# switch_eval_box_redo_v2-1.net
KiCad netlist of a schematic drawn in EAGLE
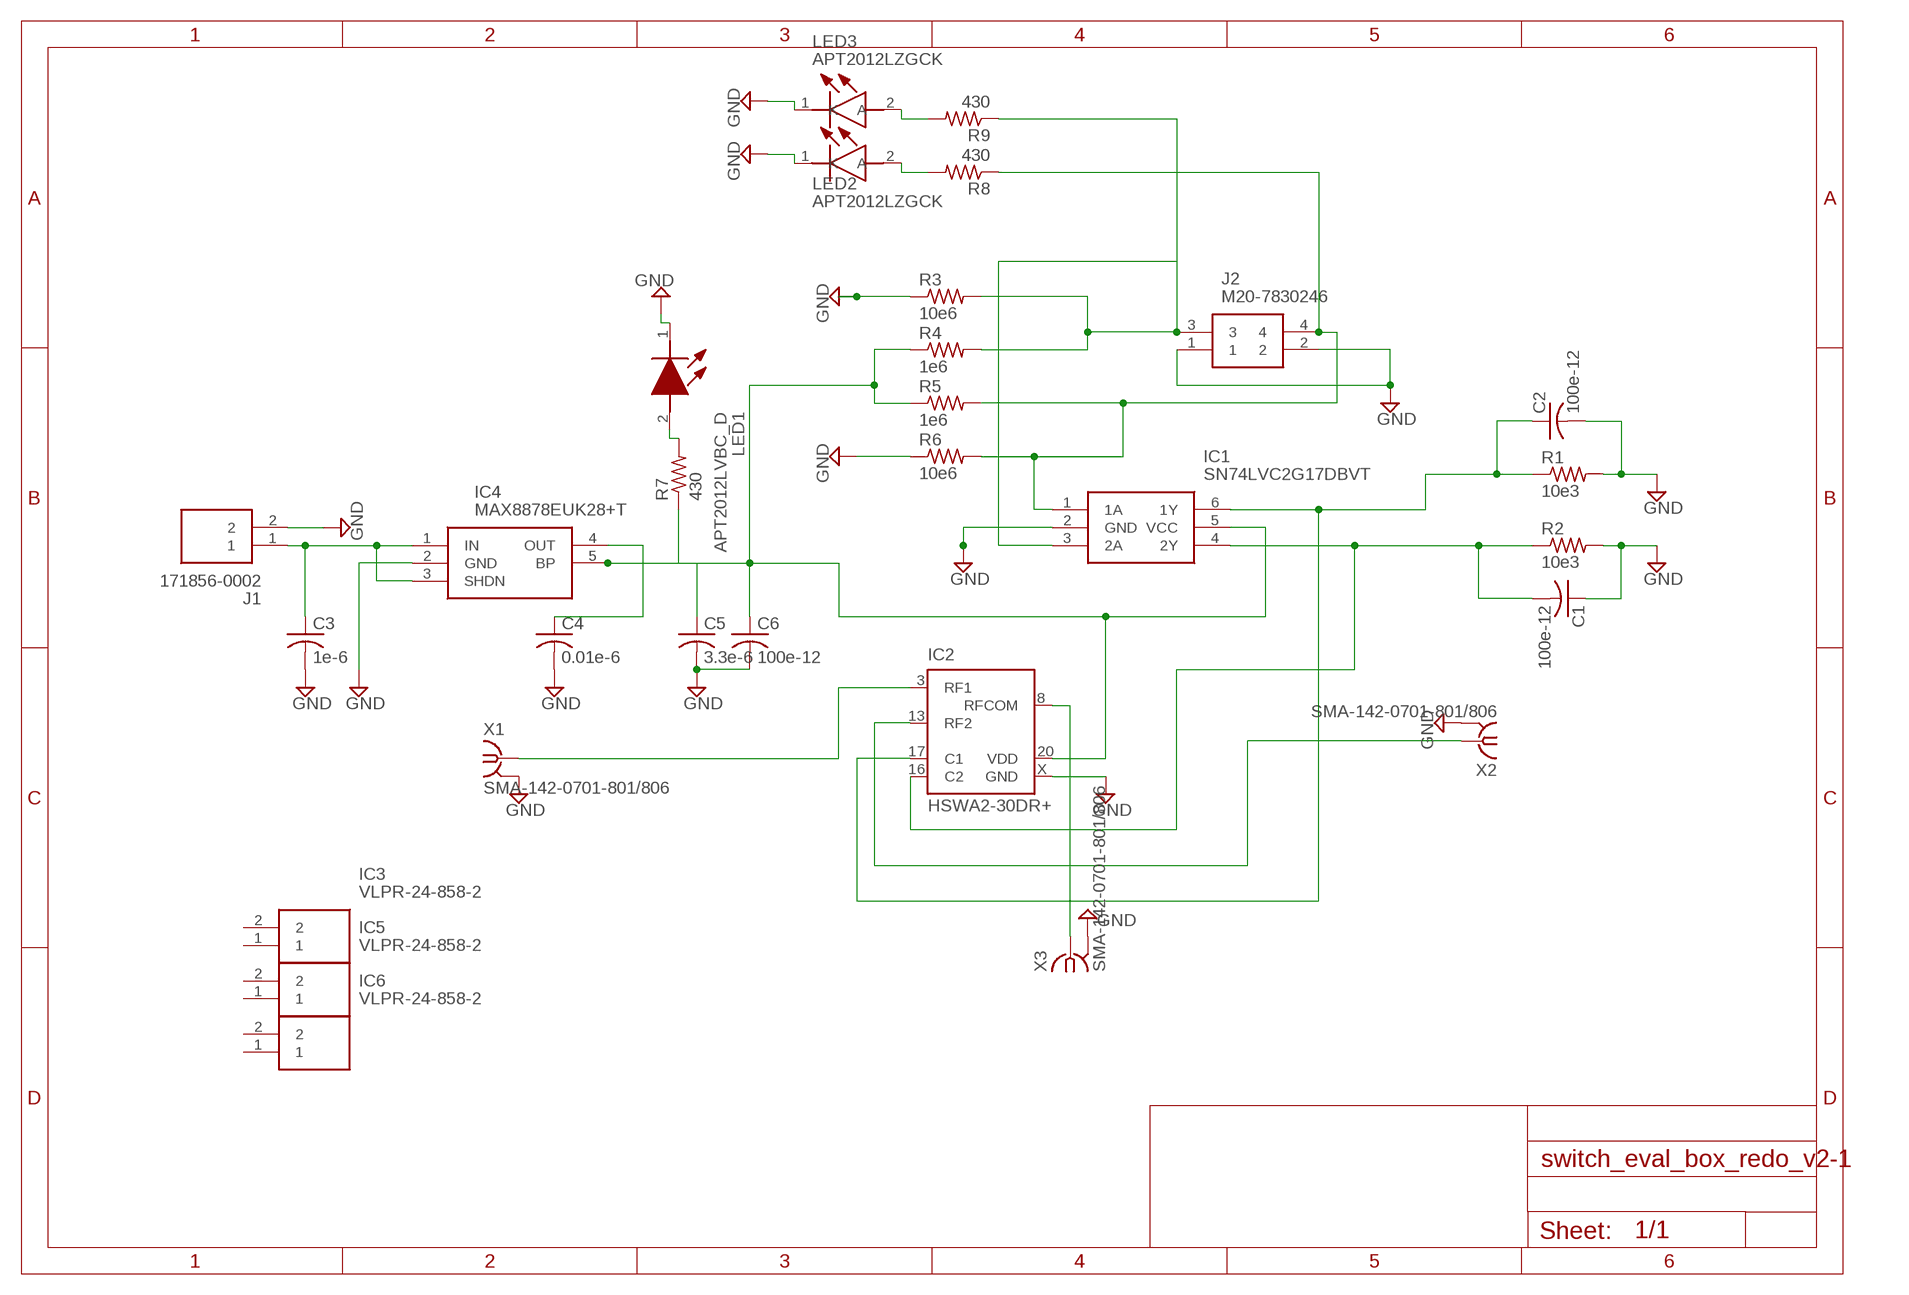
[diagram p0: schematic, sheet 1]

(export (version "E")
  (design (tool "Eeschema 10.0.6"))
  (components
    (comp (ref "C1")
      (value "100e-12")
      (footprint "eagle-import:C0603")
      (libsource (lib "eagle-import") (part "C-USC0603"))
    )
    (comp (ref "C2")
      (value "100e-12")
      (footprint "eagle-import:C0603")
      (libsource (lib "eagle-import") (part "C-USC0603"))
    )
    (comp (ref "C3")
      (value "1e-6")
      (footprint "eagle-import:C0603")
      (libsource (lib "eagle-import") (part "C-USC0603"))
    )
    (comp (ref "C4")
      (value "0.01e-6")
      (footprint "eagle-import:C0603")
      (libsource (lib "eagle-import") (part "C-USC0603"))
    )
    (comp (ref "C5")
      (value "3.3e-6")
      (footprint "eagle-import:C0603")
      (libsource (lib "eagle-import") (part "C-USC0603"))
    )
    (comp (ref "C6")
      (value "100e-12")
      (footprint "eagle-import:C0603")
      (libsource (lib "eagle-import") (part "C-USC0603"))
    )
    (comp (ref "IC1")
      (value "SN74LVC2G17DBVT")
      (footprint "eagle-import:SOT95P280X145-6N")
      (fields
        (field (name "MOUSER_PART_NUMBER") "595-SN74LVC2G17DBVT")
        (field (name "RS_PART_NUMBER") "6628944P")
      )
      (libsource (lib "eagle-import") (part "SN74LVC2G17DBVT"))
    )
    (comp (ref "IC2")
      (value "HSWA2-30DR+")
      (footprint "eagle-import:DG983-1")
      (libsource (lib "eagle-import") (part "HSWA2-30DR+"))
    )
    (comp (ref "IC3")
      (value "VLPR-24-858-2")
      (footprint "eagle-import:VLPR248582")
      (fields (field (name "RS_PART_NUMBER") "9063748"))
      (libsource (lib "eagle-import") (part "VLPR-24-858-2"))
    )
    (comp (ref "IC4")
      (value "MAX8878EUK28+T")
      (footprint "eagle-import:SOT95P280X145-5N")
      (libsource (lib "eagle-import") (part "MAX8878EUK28+T"))
    )
    (comp (ref "IC5")
      (value "VLPR-24-858-2")
      (footprint "eagle-import:VLPR248582")
      (fields (field (name "RS_PART_NUMBER") "9063748"))
      (libsource (lib "eagle-import") (part "VLPR-24-858-2"))
    )
    (comp (ref "IC6")
      (value "VLPR-24-858-2")
      (footprint "eagle-import:VLPR248582")
      (fields (field (name "RS_PART_NUMBER") "9063748"))
      (libsource (lib "eagle-import") (part "VLPR-24-858-2"))
    )
    (comp (ref "J1")
      (value "171856-0002")
      (footprint "eagle-import:SHDR2W90P0X254_1X2_493X635X106")
      (fields
        (field (name "MOUSER_PART_NUMBER") "538-171856-0002")
        (field (name "RS_PART_NUMBER") "7922884P")
      )
      (libsource (lib "eagle-import") (part "171856-0002"))
    )
    (comp (ref "J2")
      (value "M20-7830246")
      (footprint "eagle-import:M207830246")
      (fields
        (field (name "MOUSER_PART_NUMBER") "855-M20-7830246")
        (field (name "RS_PART_NUMBER") "6816839P")
      )
      (libsource (lib "eagle-import") (part "M20-7830246"))
    )
    (comp (ref "LED1")
      (value "APT2012LVBC_D")
      (footprint "eagle-import:LEDC2012X85N")
      (fields
        (field (name "ARROW_PART_NUMBER") "APT2012LVBC/D")
        (field (name "MOUSER_PART_NUMBER") "604-APT2012LVBCD")
      )
      (libsource (lib "eagle-import") (part "APT2012LVBC_D"))
    )
    (comp (ref "LED2")
      (value "APT2012LZGCK")
      (footprint "eagle-import:LEDC2012X85N")
      (fields (field (name "MOUSER_PART_NUMBER") "604-APT2012LZGCK"))
      (libsource (lib "eagle-import") (part "APT2012LZGCK"))
    )
    (comp (ref "LED3")
      (value "APT2012LZGCK")
      (footprint "eagle-import:LEDC2012X85N")
      (fields (field (name "MOUSER_PART_NUMBER") "604-APT2012LZGCK"))
      (libsource (lib "eagle-import") (part "APT2012LZGCK"))
    )
    (comp (ref "R1")
      (value "10e3")
      (footprint "eagle-import:R0603")
      (libsource (lib "eagle-import") (part "R-US_R0603"))
    )
    (comp (ref "R2")
      (value "10e3")
      (footprint "eagle-import:R0603")
      (libsource (lib "eagle-import") (part "R-US_R0603"))
    )
    (comp (ref "R3")
      (value "10e6")
      (footprint "eagle-import:R0603")
      (libsource (lib "eagle-import") (part "R-US_R0603"))
    )
    (comp (ref "R4")
      (value "1e6")
      (footprint "eagle-import:R0603")
      (libsource (lib "eagle-import") (part "R-US_R0603"))
    )
    (comp (ref "R5")
      (value "1e6")
      (footprint "eagle-import:R0603")
      (libsource (lib "eagle-import") (part "R-US_R0603"))
    )
    (comp (ref "R6")
      (value "10e6")
      (footprint "eagle-import:R0603")
      (libsource (lib "eagle-import") (part "R-US_R0603"))
    )
    (comp (ref "R7")
      (value "430")
      (footprint "eagle-import:R0603")
      (libsource (lib "eagle-import") (part "R-US_R0603"))
    )
    (comp (ref "R8")
      (value "430")
      (footprint "eagle-import:R0603")
      (libsource (lib "eagle-import") (part "R-US_R0603"))
    )
    (comp (ref "R9")
      (value "430")
      (footprint "eagle-import:R0603")
      (libsource (lib "eagle-import") (part "R-US_R0603"))
    )
    (comp (ref "X1")
      (value "SMA-142-0701-801/806")
      (footprint "eagle-import:J502-ND-142-0701-801_806")
      (fields (field (name "MF") "JOHNSON COMPONENTS") (field (name "MPN") "142-0701-801"))
      (libsource (lib "eagle-import") (part "SMA-142-0701-801/806"))
    )
    (comp (ref "X2")
      (value "SMA-142-0701-801/806")
      (footprint "eagle-import:J502-ND-142-0701-801_806")
      (fields (field (name "MF") "JOHNSON COMPONENTS") (field (name "MPN") "142-0701-801"))
      (libsource (lib "eagle-import") (part "SMA-142-0701-801/806"))
    )
    (comp (ref "X3")
      (value "SMA-142-0701-801/806")
      (footprint "eagle-import:J502-ND-142-0701-801_806")
      (fields (field (name "MF") "JOHNSON COMPONENTS") (field (name "MPN") "142-0701-801"))
      (libsource (lib "eagle-import") (part "SMA-142-0701-801/806"))
    )
  )
  (nets
    (net (code "1") (name "GND") (class "Default")
      (node (ref "C1") (pin "1") (pinfunction "1_1") (pintype "passive"))
      (node (ref "C2") (pin "2") (pinfunction "2_2") (pintype "passive"))
      (node (ref "C3") (pin "2") (pinfunction "2_2") (pintype "passive"))
      (node (ref "C4") (pin "2") (pinfunction "2_2") (pintype "passive"))
      (node (ref "C5") (pin "2") (pinfunction "2_2") (pintype "passive"))
      (node (ref "C6") (pin "2") (pinfunction "2_2") (pintype "passive"))
      (node (ref "IC1") (pin "2") (pinfunction "GND_2") (pintype "bidirectional"))
      (node (ref "IC2") (pin "X") (pinfunction "GND_X") (pintype "power_in"))
      (node (ref "IC4") (pin "2") (pinfunction "GND_2") (pintype "power_in"))
      (node (ref "J1") (pin "2") (pinfunction "2_2") (pintype "bidirectional"))
      (node (ref "J2") (pin "1") (pinfunction "1_1") (pintype "bidirectional"))
      (node (ref "J2") (pin "2") (pinfunction "2_2") (pintype "bidirectional"))
      (node (ref "LED1") (pin "1") (pinfunction "K_1") (pintype "bidirectional"))
      (node (ref "LED2") (pin "1") (pinfunction "K_1") (pintype "bidirectional"))
      (node (ref "LED3") (pin "1") (pinfunction "K_1") (pintype "bidirectional"))
      (node (ref "R1") (pin "2") (pinfunction "2_2") (pintype "passive"))
      (node (ref "R2") (pin "2") (pinfunction "2_2") (pintype "passive"))
      (node (ref "R3") (pin "1") (pinfunction "1_1") (pintype "passive"))
      (node (ref "R6") (pin "1") (pinfunction "1_1") (pintype "passive"))
      (node (ref "X1") (pin "G@1") (pinfunction "2_G@1") (pintype "passive"))
      (node (ref "X1") (pin "G@2") (pinfunction "2_G@2") (pintype "passive"))
      (node (ref "X1") (pin "G@3") (pinfunction "2_G@3") (pintype "passive"))
      (node (ref "X1") (pin "G@4") (pinfunction "2_G@4") (pintype "passive"))
      (node (ref "X2") (pin "G@1") (pinfunction "2_G@1") (pintype "passive"))
      (node (ref "X2") (pin "G@2") (pinfunction "2_G@2") (pintype "passive"))
      (node (ref "X2") (pin "G@3") (pinfunction "2_G@3") (pintype "passive"))
      (node (ref "X2") (pin "G@4") (pinfunction "2_G@4") (pintype "passive"))
      (node (ref "X3") (pin "G@1") (pinfunction "2_G@1") (pintype "passive"))
      (node (ref "X3") (pin "G@2") (pinfunction "2_G@2") (pintype "passive"))
      (node (ref "X3") (pin "G@3") (pinfunction "2_G@3") (pintype "passive"))
      (node (ref "X3") (pin "G@4") (pinfunction "2_G@4") (pintype "passive"))
    )
    (net (code "2") (name "Net-(IC1-1A)") (class "Default")
      (node (ref "IC1") (pin "1") (pinfunction "1A_1") (pintype "bidirectional"))
      (node (ref "J2") (pin "4") (pinfunction "4_4") (pintype "bidirectional"))
      (node (ref "R5") (pin "2") (pinfunction "2_2") (pintype "passive"))
      (node (ref "R6") (pin "2") (pinfunction "2_2") (pintype "passive"))
      (node (ref "R8") (pin "1") (pinfunction "1_1") (pintype "passive"))
    )
    (net (code "3") (name "Net-(IC1-1Y)") (class "Default")
      (node (ref "C2") (pin "1") (pinfunction "1_1") (pintype "passive"))
      (node (ref "IC1") (pin "6") (pinfunction "1Y_6") (pintype "bidirectional"))
      (node (ref "IC2") (pin "17") (pinfunction "C1_17") (pintype "passive"))
      (node (ref "R1") (pin "1") (pinfunction "1_1") (pintype "passive"))
    )
    (net (code "4") (name "Net-(IC1-2A)") (class "Default")
      (node (ref "IC1") (pin "3") (pinfunction "2A_3") (pintype "bidirectional"))
      (node (ref "J2") (pin "3") (pinfunction "3_3") (pintype "bidirectional"))
      (node (ref "R3") (pin "2") (pinfunction "2_2") (pintype "passive"))
      (node (ref "R4") (pin "2") (pinfunction "2_2") (pintype "passive"))
      (node (ref "R9") (pin "1") (pinfunction "1_1") (pintype "passive"))
    )
    (net (code "5") (name "Net-(IC1-2Y)") (class "Default")
      (node (ref "C1") (pin "2") (pinfunction "2_2") (pintype "passive"))
      (node (ref "IC1") (pin "4") (pinfunction "2Y_4") (pintype "bidirectional"))
      (node (ref "IC2") (pin "16") (pinfunction "C2_16") (pintype "passive"))
      (node (ref "R2") (pin "1") (pinfunction "1_1") (pintype "passive"))
    )
    (net (code "6") (name "Net-(IC1-VCC)") (class "Default")
      (node (ref "C5") (pin "1") (pinfunction "1_1") (pintype "passive"))
      (node (ref "C6") (pin "1") (pinfunction "1_1") (pintype "passive"))
      (node (ref "IC1") (pin "5") (pinfunction "VCC_5") (pintype "bidirectional"))
      (node (ref "IC2") (pin "20") (pinfunction "VDD_20") (pintype "input"))
      (node (ref "IC4") (pin "5") (pinfunction "BP_5") (pintype "bidirectional"))
      (node (ref "R4") (pin "1") (pinfunction "1_1") (pintype "passive"))
      (node (ref "R5") (pin "1") (pinfunction "1_1") (pintype "passive"))
      (node (ref "R7") (pin "1") (pinfunction "1_1") (pintype "passive"))
    )
    (net (code "7") (name "Net-(IC2A-RF1)") (class "Default")
      (node (ref "IC2") (pin "3") (pinfunction "RF1_3") (pintype "passive"))
      (node (ref "X1") (pin "1") (pinfunction "1_1") (pintype "passive"))
    )
    (net (code "8") (name "Net-(IC2A-RF2)") (class "Default")
      (node (ref "IC2") (pin "13") (pinfunction "RF2_13") (pintype "passive"))
      (node (ref "X2") (pin "1") (pinfunction "1_1") (pintype "passive"))
    )
    (net (code "9") (name "Net-(IC2A-RFCOM)") (class "Default")
      (node (ref "IC2") (pin "8") (pinfunction "RFCOM_8") (pintype "passive"))
      (node (ref "X3") (pin "1") (pinfunction "1_1") (pintype "passive"))
    )
    (net (code "10") (name "Net-(IC4-IN)") (class "Default")
      (node (ref "C3") (pin "1") (pinfunction "1_1") (pintype "passive"))
      (node (ref "IC4") (pin "1") (pinfunction "IN_1") (pintype "input"))
      (node (ref "IC4") (pin "3") (pinfunction "SHDN_3") (pintype "bidirectional"))
      (node (ref "J1") (pin "1") (pinfunction "1_1") (pintype "bidirectional"))
    )
    (net (code "11") (name "Net-(IC4-OUT)") (class "Default")
      (node (ref "C4") (pin "1") (pinfunction "1_1") (pintype "passive"))
      (node (ref "IC4") (pin "4") (pinfunction "OUT_4") (pintype "output"))
    )
    (net (code "12") (name "Net-(LED1-A)") (class "Default")
      (node (ref "LED1") (pin "2") (pinfunction "A_2") (pintype "bidirectional"))
      (node (ref "R7") (pin "2") (pinfunction "2_2") (pintype "passive"))
    )
    (net (code "13") (name "Net-(LED2-A)") (class "Default")
      (node (ref "LED2") (pin "2") (pinfunction "A_2") (pintype "bidirectional"))
      (node (ref "R8") (pin "2") (pinfunction "2_2") (pintype "passive"))
    )
    (net (code "14") (name "Net-(LED3-A)") (class "Default")
      (node (ref "LED3") (pin "2") (pinfunction "A_2") (pintype "bidirectional"))
      (node (ref "R9") (pin "2") (pinfunction "2_2") (pintype "passive"))
    )
    (net (code "15") (name "unconnected-(IC3-Pad1)") (class "Default")
      (node (ref "IC3") (pin "1") (pinfunction "1_1") (pintype "bidirectional"))
    )
    (net (code "16") (name "unconnected-(IC3-Pad2)") (class "Default")
      (node (ref "IC3") (pin "2") (pinfunction "2_2") (pintype "bidirectional"))
    )
    (net (code "17") (name "unconnected-(IC5-Pad1)") (class "Default")
      (node (ref "IC5") (pin "1") (pinfunction "1_1") (pintype "bidirectional"))
    )
    (net (code "18") (name "unconnected-(IC5-Pad2)") (class "Default")
      (node (ref "IC5") (pin "2") (pinfunction "2_2") (pintype "bidirectional"))
    )
    (net (code "19") (name "unconnected-(IC6-Pad1)") (class "Default")
      (node (ref "IC6") (pin "1") (pinfunction "1_1") (pintype "bidirectional"))
    )
    (net (code "20") (name "unconnected-(IC6-Pad2)") (class "Default")
      (node (ref "IC6") (pin "2") (pinfunction "2_2") (pintype "bidirectional"))
    )
  )
)
